# CAN_Transceiver.net
KiCad netlist of a schematic drawn in Altium Designer
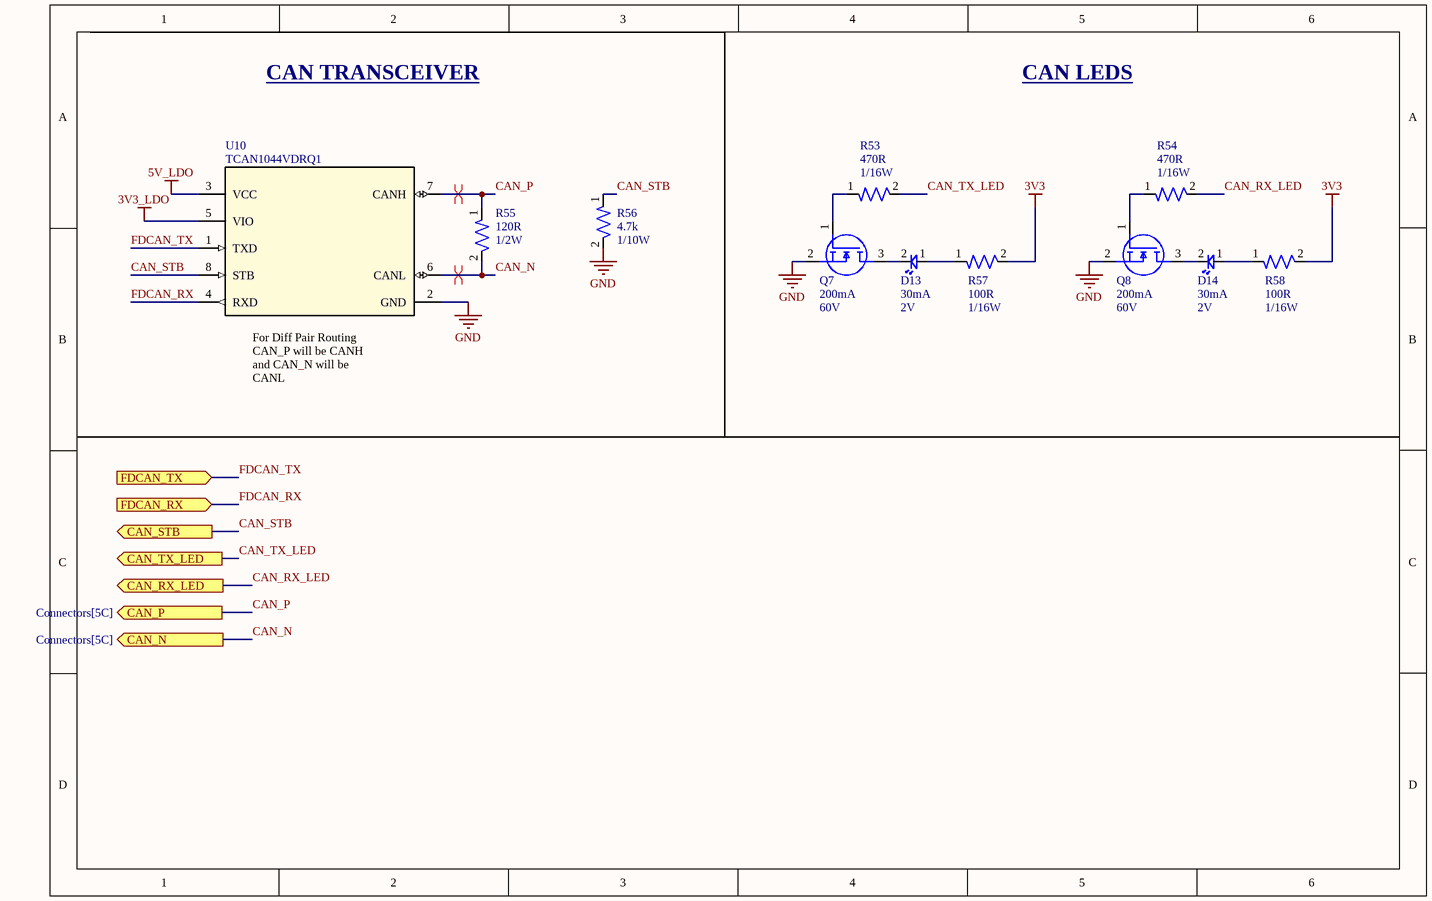
[diagram p0: CAN_Transceiver.SchDoc]

(export (version "E")
  (design (tool "Eeschema 10.0.6"))
  (components
    (comp (ref "D13")
      (value "BL-HKC36G-AV-TRB")
      (footprint "LED-0603")
      (description "LED YELLOW CLEAR 0603 SMD")
      (fields (field (name "FORWARD CURRENT") "30mA") (field (name "FORWARD VOLTAGE") "2V"))
      (libsource (lib "JLC_25") (part "LED-0001"))
    )
    (comp (ref "D14")
      (value "BL-HKC36G-AV-TRB")
      (footprint "LED-0603")
      (description "LED YELLOW CLEAR 0603 SMD")
      (fields (field (name "FORWARD CURRENT") "30mA") (field (name "FORWARD VOLTAGE") "2V"))
      (libsource (lib "JLC_25") (part "LED-0001"))
    )
    (comp (ref "Q7")
      (value "T2N7002AK,LM")
      (footprint "IC-SOT23-3")
      (description "MOSFET N-CH 60V 200MA SOT23")
      (fields (field (name "CONTINUOUS CURRENT") "200mA") (field (name "VOLTAGE") "60V"))
      (libsource (lib "JLC_25") (part "NMOS-200MA-0001"))
    )
    (comp (ref "Q8")
      (value "T2N7002AK,LM")
      (footprint "IC-SOT23-3")
      (description "MOSFET N-CH 60V 200MA SOT23")
      (fields (field (name "CONTINUOUS CURRENT") "200mA") (field (name "VOLTAGE") "60V"))
      (libsource (lib "JLC_25") (part "NMOS-200MA-0001"))
    )
    (comp (ref "R53")
      (value "RC0402FR-07470RL")
      (footprint "RES-0402")
      (description "RES 470 OHM 1% 1/16W 0402")
      (fields
        (field (name "TOLERANCE") "1%")
        (field (name "POWER") "1/16W")
        (field (name "RESISTANCE") "470R")
      )
      (libsource (lib "JLC_25") (part "RES-470-0001"))
    )
    (comp (ref "R54")
      (value "RC0402FR-07470RL")
      (footprint "RES-0402")
      (description "RES 470 OHM 1% 1/16W 0402")
      (fields
        (field (name "TOLERANCE") "1%")
        (field (name "POWER") "1/16W")
        (field (name "RESISTANCE") "470R")
      )
      (libsource (lib "JLC_25") (part "RES-470-0001"))
    )
    (comp (ref "R55")
      (value "RC1210FR-07120RL")
      (footprint "RES-1210")
      (description "RES 120 OHM 1% 1/2W 1210")
      (fields
        (field (name "TOLERANCE") "1%")
        (field (name "POWER") "1/2W")
        (field (name "RESISTANCE") "120R")
      )
      (libsource (lib "JLC_25") (part "RES-120-0001"))
    )
    (comp (ref "R56")
      (value "RC0603FR-074K7L")
      (footprint "RES-0603")
      (description "RES 4.7K OHM 1% 1/10W 0603")
      (fields
        (field (name "TOLERANCE") "1%")
        (field (name "POWER") "1/10W")
        (field (name "RESISTANCE") "4.7k")
      )
      (libsource (lib "JLC_25") (part "RES-4.7k-0001"))
    )
    (comp (ref "R57")
      (value "RC0402FR-07100RL")
      (footprint "RES-0402")
      (description "RES 100 OHM 1% 1/16W 0402")
      (fields
        (field (name "TOLERANCE") "1%")
        (field (name "POWER") "1/16W")
        (field (name "RESISTANCE") "100R")
      )
      (libsource (lib "JLC_25") (part "RES-100-0001"))
    )
    (comp (ref "R58")
      (value "RC0402FR-07100RL")
      (footprint "RES-0402")
      (description "RES 100 OHM 1% 1/16W 0402")
      (fields
        (field (name "TOLERANCE") "1%")
        (field (name "POWER") "1/16W")
        (field (name "RESISTANCE") "100R")
      )
      (libsource (lib "JLC_25") (part "RES-100-0001"))
    )
    (comp (ref "U10")
      (value "TCAN1044VDRQ1")
      (footprint "IC-8SOIC")
      (description "IC TRANSCEIVER 1/1 8SOIC")
      (libsource (lib "JLC_25") (part "IC-CAN-0001"))
    )
  )
  (nets
    (net (code "1") (name "/CAN_N") (class "Default")
      (node (ref "R55") (pin "2") (pinfunction "2_2") (pintype "passive"))
      (node (ref "U10") (pin "6") (pinfunction "CANL_6") (pintype "bidirectional"))
    )
    (net (code "2") (name "/CAN_P") (class "Default")
      (node (ref "R55") (pin "1") (pinfunction "1_1") (pintype "passive"))
      (node (ref "U10") (pin "7") (pinfunction "CANH_7") (pintype "bidirectional"))
    )
    (net (code "3") (name "/CAN_RX_LED") (class "Default")
      (node (ref "R54") (pin "2") (pinfunction "2_2") (pintype "passive"))
    )
    (net (code "4") (name "/CAN_STB") (class "Default")
      (node (ref "R56") (pin "1") (pinfunction "1_1") (pintype "passive"))
      (node (ref "U10") (pin "8") (pinfunction "STB_8") (pintype "input"))
    )
    (net (code "5") (name "/CAN_TX_LED") (class "Default")
      (node (ref "R53") (pin "2") (pinfunction "2_2") (pintype "passive"))
    )
    (net (code "6") (name "/FDCAN_RX") (class "Default")
      (node (ref "U10") (pin "4") (pinfunction "RXD_4") (pintype "output"))
    )
    (net (code "7") (name "/FDCAN_TX") (class "Default")
      (node (ref "U10") (pin "1") (pinfunction "TXD_1") (pintype "input"))
    )
    (net (code "8") (name "3V3") (class "Default")
      (node (ref "R57") (pin "2") (pinfunction "2_2") (pintype "passive"))
      (node (ref "R58") (pin "2") (pinfunction "2_2") (pintype "passive"))
    )
    (net (code "9") (name "3V3_LDO") (class "Default")
      (node (ref "U10") (pin "5") (pinfunction "VIO_5") (pintype "power_in"))
    )
    (net (code "10") (name "5V_LDO") (class "Default")
      (node (ref "U10") (pin "3") (pinfunction "VCC_3") (pintype "power_in"))
    )
    (net (code "11") (name "GND") (class "Default")
      (node (ref "Q7") (pin "2") (pinfunction "S_2") (pintype "passive"))
      (node (ref "Q8") (pin "2") (pinfunction "S_2") (pintype "passive"))
      (node (ref "R56") (pin "2") (pinfunction "2_2") (pintype "passive"))
      (node (ref "U10") (pin "2") (pinfunction "GND_2") (pintype "power_in"))
    )
    (net (code "12") (name "Net-(D13-Pad1)") (class "Default")
      (node (ref "D13") (pin "1") (pinfunction "1_1") (pintype "passive"))
      (node (ref "R57") (pin "1") (pinfunction "1_1") (pintype "passive"))
    )
    (net (code "13") (name "Net-(D14-Pad1)") (class "Default")
      (node (ref "D14") (pin "1") (pinfunction "1_1") (pintype "passive"))
      (node (ref "R58") (pin "1") (pinfunction "1_1") (pintype "passive"))
    )
    (net (code "14") (name "Net-(Q7-D)") (class "Default")
      (node (ref "D13") (pin "2") (pinfunction "2_2") (pintype "passive"))
      (node (ref "Q7") (pin "3") (pinfunction "D_3") (pintype "passive"))
    )
    (net (code "15") (name "Net-(Q7-G)") (class "Default")
      (node (ref "Q7") (pin "1") (pinfunction "G_1") (pintype "passive"))
      (node (ref "R53") (pin "1") (pinfunction "1_1") (pintype "passive"))
    )
    (net (code "16") (name "Net-(Q8-D)") (class "Default")
      (node (ref "D14") (pin "2") (pinfunction "2_2") (pintype "passive"))
      (node (ref "Q8") (pin "3") (pinfunction "D_3") (pintype "passive"))
    )
    (net (code "17") (name "Net-(Q8-G)") (class "Default")
      (node (ref "Q8") (pin "1") (pinfunction "G_1") (pintype "passive"))
      (node (ref "R54") (pin "1") (pinfunction "1_1") (pintype "passive"))
    )
  )
)
